# Board-Front.net
KiCad netlist of a schematic drawn in EAGLE
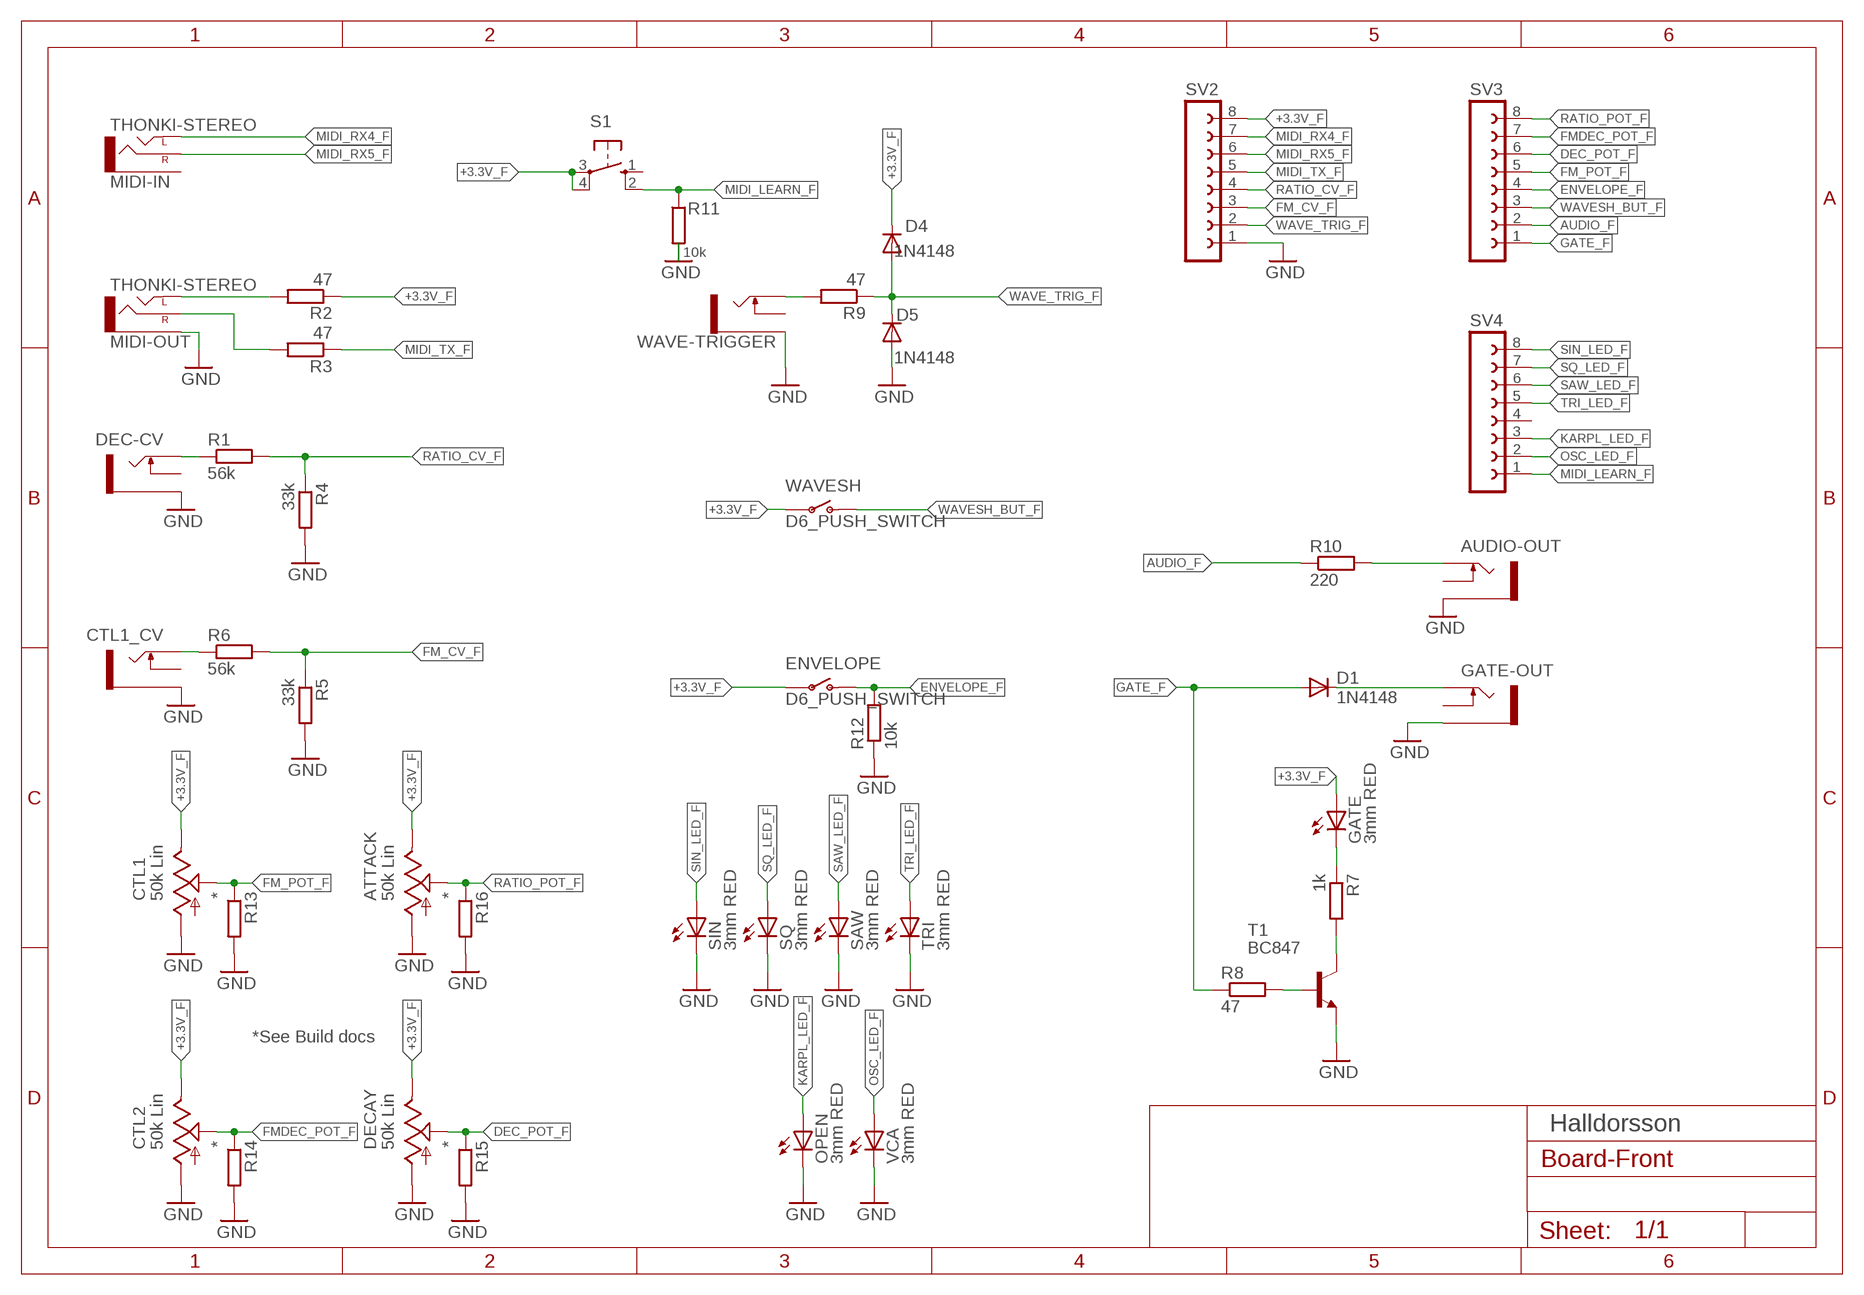
[diagram p0: schematic, sheet 1]

(export (version "E")
  (design (tool "Eeschema 10.0.6"))
  (components
    (comp (ref "ATTACK")
      (value "50k Lin")
      (footprint "eagle-import:9MM_SNAP-IN_POT")
      (libsource (lib "eagle-import") (part "9MM_SNAP-IN_POT_"))
    )
    (comp (ref "AUDIO-OUT")
      (value "THONKICONNNEW")
      (footprint "eagle-import:WQP-PJ301M-12_JACK")
      (libsource (lib "eagle-import") (part "THONKICONNNEW"))
    )
    (comp (ref "CTL1")
      (value "50k Lin")
      (footprint "eagle-import:9MM_SNAP-IN_POT")
      (libsource (lib "eagle-import") (part "9MM_SNAP-IN_POT_"))
    )
    (comp (ref "CTL1_CV")
      (value "THONKICONNNEW")
      (footprint "eagle-import:WQP-PJ301M-12_JACK")
      (libsource (lib "eagle-import") (part "THONKICONNNEW"))
    )
    (comp (ref "CTL2")
      (value "50k Lin")
      (footprint "eagle-import:9MM_SNAP-IN_POT")
      (libsource (lib "eagle-import") (part "9MM_SNAP-IN_POT_"))
    )
    (comp (ref "D1")
      (value "1N4148")
      (footprint "eagle-import:DO35-7")
      (libsource (lib "eagle-import") (part "1N4148DO35-7"))
    )
    (comp (ref "D4")
      (value "1N4148")
      (footprint "eagle-import:DO35-7")
      (libsource (lib "eagle-import") (part "1N4148DO35-7"))
    )
    (comp (ref "D5")
      (value "1N4148")
      (footprint "eagle-import:DO35-7")
      (libsource (lib "eagle-import") (part "1N4148DO35-7"))
    )
    (comp (ref "DEC-CV")
      (value "THONKICONNNEW")
      (footprint "eagle-import:WQP-PJ301M-12_JACK")
      (libsource (lib "eagle-import") (part "THONKICONNNEW"))
    )
    (comp (ref "DECAY")
      (value "50k Lin")
      (footprint "eagle-import:9MM_SNAP-IN_POT")
      (libsource (lib "eagle-import") (part "9MM_SNAP-IN_POT_"))
    )
    (comp (ref "ENVELOPE")
      (value "D6_PUSH_SWITCH")
      (footprint "eagle-import:D6_PUSH_SWITCH")
      (libsource (lib "eagle-import") (part "D6_PUSH_SWITCH"))
    )
    (comp (ref "GATE")
      (value "3mm RED")
      (footprint "eagle-import:LED3MM")
      (libsource (lib "eagle-import") (part "LED3MM"))
    )
    (comp (ref "GATE-OUT")
      (value "THONKICONNNEW")
      (footprint "eagle-import:WQP-PJ301M-12_JACK")
      (libsource (lib "eagle-import") (part "THONKICONNNEW"))
    )
    (comp (ref "MIDI-IN")
      (value "THONKI-STEREO")
      (footprint "eagle-import:WQP-PJ366ST_JACK")
      (libsource (lib "eagle-import") (part "THONKI-STEREO"))
    )
    (comp (ref "MIDI-OUT")
      (value "THONKI-STEREO")
      (footprint "eagle-import:WQP-PJ366ST_JACK")
      (libsource (lib "eagle-import") (part "THONKI-STEREO"))
    )
    (comp (ref "OPEN")
      (value "3mm RED")
      (footprint "eagle-import:LED3MM")
      (libsource (lib "eagle-import") (part "LED3MM"))
    )
    (comp (ref "R1")
      (value "56k")
      (footprint "eagle-import:M1206")
      (libsource (lib "eagle-import") (part "R-EU_M1206"))
    )
    (comp (ref "R2")
      (value "47")
      (footprint "eagle-import:M1206")
      (libsource (lib "eagle-import") (part "R-EU_M1206"))
    )
    (comp (ref "R3")
      (value "47")
      (footprint "eagle-import:M1206")
      (libsource (lib "eagle-import") (part "R-EU_M1206"))
    )
    (comp (ref "R4")
      (value "33k")
      (footprint "eagle-import:M1206")
      (libsource (lib "eagle-import") (part "R-EU_M1206"))
    )
    (comp (ref "R5")
      (value "33k")
      (footprint "eagle-import:M1206")
      (libsource (lib "eagle-import") (part "R-EU_M1206"))
    )
    (comp (ref "R6")
      (value "56k")
      (footprint "eagle-import:M1206")
      (libsource (lib "eagle-import") (part "R-EU_M1206"))
    )
    (comp (ref "R7")
      (value "1k")
      (footprint "eagle-import:M1206")
      (libsource (lib "eagle-import") (part "R-EU_M1206"))
    )
    (comp (ref "R8")
      (value "47")
      (footprint "eagle-import:M1206")
      (libsource (lib "eagle-import") (part "R-EU_M1206"))
    )
    (comp (ref "R9")
      (value "47")
      (footprint "eagle-import:M1206")
      (libsource (lib "eagle-import") (part "R-EU_M1206"))
    )
    (comp (ref "R10")
      (value "220")
      (footprint "eagle-import:M1206")
      (libsource (lib "eagle-import") (part "R-EU_M1206"))
    )
    (comp (ref "R11")
      (value "10k")
      (footprint "eagle-import:M1206")
      (libsource (lib "eagle-import") (part "R-EU_M1206"))
    )
    (comp (ref "R12")
      (value "10k")
      (footprint "eagle-import:M1206")
      (libsource (lib "eagle-import") (part "R-EU_M1206"))
    )
    (comp (ref "R13")
      (value "*")
      (footprint "eagle-import:M1206")
      (libsource (lib "eagle-import") (part "R-EU_M1206"))
    )
    (comp (ref "R14")
      (value "*")
      (footprint "eagle-import:M1206")
      (libsource (lib "eagle-import") (part "R-EU_M1206"))
    )
    (comp (ref "R15")
      (value "*")
      (footprint "eagle-import:M1206")
      (libsource (lib "eagle-import") (part "R-EU_M1206"))
    )
    (comp (ref "R16")
      (value "*")
      (footprint "eagle-import:M1206")
      (libsource (lib "eagle-import") (part "R-EU_M1206"))
    )
    (comp (ref "S1")
      (value "10-XX")
      (footprint "eagle-import:B3F-10XX")
      (fields (field (name "MPN") "B3F-1000"))
      (libsource (lib "eagle-import") (part "10-XX"))
    )
    (comp (ref "SAW")
      (value "3mm RED")
      (footprint "eagle-import:LED3MM")
      (libsource (lib "eagle-import") (part "LED3MM"))
    )
    (comp (ref "SIN")
      (value "3mm RED")
      (footprint "eagle-import:LED3MM")
      (libsource (lib "eagle-import") (part "LED3MM"))
    )
    (comp (ref "SQ")
      (value "3mm RED")
      (footprint "eagle-import:LED3MM")
      (libsource (lib "eagle-import") (part "LED3MM"))
    )
    (comp (ref "SV2")
      (value "FE08-1")
      (footprint "eagle-import:FE08")
      (libsource (lib "eagle-import") (part "FE08-1"))
    )
    (comp (ref "SV3")
      (value "FE08-1")
      (footprint "eagle-import:FE08")
      (libsource (lib "eagle-import") (part "FE08-1"))
    )
    (comp (ref "SV4")
      (value "FE08-1")
      (footprint "eagle-import:FE08")
      (libsource (lib "eagle-import") (part "FE08-1"))
    )
    (comp (ref "T1")
      (value "BC847")
      (footprint "eagle-import:SOT23")
      (libsource (lib "eagle-import") (part "BC847"))
    )
    (comp (ref "TRI")
      (value "3mm RED")
      (footprint "eagle-import:LED3MM")
      (libsource (lib "eagle-import") (part "LED3MM"))
    )
    (comp (ref "VCA")
      (value "3mm RED")
      (footprint "eagle-import:LED3MM")
      (libsource (lib "eagle-import") (part "LED3MM"))
    )
    (comp (ref "WAVE-TRIGGER")
      (value "THONKICONNNEW")
      (footprint "eagle-import:WQP-PJ301M-12_JACK")
      (libsource (lib "eagle-import") (part "THONKICONNNEW"))
    )
    (comp (ref "WAVESH")
      (value "D6_PUSH_SWITCH")
      (footprint "eagle-import:D6_PUSH_SWITCH")
      (libsource (lib "eagle-import") (part "D6_PUSH_SWITCH"))
    )
  )
  (nets
    (net (code "1") (name "+3.3V_F") (class "Default")
      (node (ref "ATTACK") (pin "3") (pinfunction "E_3") (pintype "passive"))
      (node (ref "CTL1") (pin "3") (pinfunction "E_3") (pintype "passive"))
      (node (ref "CTL2") (pin "3") (pinfunction "E_3") (pintype "passive"))
      (node (ref "D4") (pin "C") (pinfunction "C_C") (pintype "passive"))
      (node (ref "DECAY") (pin "3") (pinfunction "E_3") (pintype "passive"))
      (node (ref "ENVELOPE") (pin "P$3") (pinfunction "P_P$3") (pintype "passive"))
      (node (ref "ENVELOPE") (pin "P$4") (pinfunction "P_P$4") (pintype "passive"))
      (node (ref "GATE") (pin "A") (pinfunction "A_A") (pintype "passive"))
      (node (ref "R2") (pin "1") (pinfunction "1_1") (pintype "passive"))
      (node (ref "S1") (pin "3") (pinfunction "P_3") (pintype "passive"))
      (node (ref "S1") (pin "4") (pinfunction "P1_4") (pintype "passive"))
      (node (ref "SV2") (pin "8") (pinfunction "8_8") (pintype "passive"))
      (node (ref "WAVESH") (pin "P$3") (pinfunction "P_P$3") (pintype "passive"))
      (node (ref "WAVESH") (pin "P$4") (pinfunction "P_P$4") (pintype "passive"))
    )
    (net (code "2") (name "AUDIO_F") (class "Default")
      (node (ref "R10") (pin "1") (pinfunction "1_1") (pintype "passive"))
      (node (ref "SV3") (pin "2") (pinfunction "2_2") (pintype "passive"))
    )
    (net (code "3") (name "DEC_POT_F") (class "Default")
      (node (ref "DECAY") (pin "2") (pinfunction "S_2") (pintype "passive"))
      (node (ref "R15") (pin "1") (pinfunction "1_1") (pintype "passive"))
      (node (ref "SV3") (pin "6") (pinfunction "6_6") (pintype "passive"))
    )
    (net (code "4") (name "ENVELOPE_F") (class "Default")
      (node (ref "ENVELOPE") (pin "P$1") (pinfunction "O_P$1") (pintype "passive"))
      (node (ref "ENVELOPE") (pin "P$2") (pinfunction "O_P$2") (pintype "passive"))
      (node (ref "R12") (pin "2") (pinfunction "2_2") (pintype "passive"))
      (node (ref "SV3") (pin "4") (pinfunction "4_4") (pintype "passive"))
    )
    (net (code "5") (name "FMDEC_POT_F") (class "Default")
      (node (ref "CTL2") (pin "2") (pinfunction "S_2") (pintype "passive"))
      (node (ref "R14") (pin "1") (pinfunction "1_1") (pintype "passive"))
      (node (ref "SV3") (pin "7") (pinfunction "7_7") (pintype "passive"))
    )
    (net (code "6") (name "FM_CV_F") (class "Default")
      (node (ref "R5") (pin "1") (pinfunction "1_1") (pintype "passive"))
      (node (ref "R6") (pin "2") (pinfunction "2_2") (pintype "passive"))
      (node (ref "SV2") (pin "3") (pinfunction "3_3") (pintype "passive"))
    )
    (net (code "7") (name "FM_POT_F") (class "Default")
      (node (ref "CTL1") (pin "2") (pinfunction "S_2") (pintype "passive"))
      (node (ref "R13") (pin "1") (pinfunction "1_1") (pintype "passive"))
      (node (ref "SV3") (pin "5") (pinfunction "5_5") (pintype "passive"))
    )
    (net (code "8") (name "GATE_F") (class "Default")
      (node (ref "D1") (pin "A") (pinfunction "A_A") (pintype "passive"))
      (node (ref "R8") (pin "1") (pinfunction "1_1") (pintype "passive"))
      (node (ref "SV3") (pin "1") (pinfunction "1_1") (pintype "passive"))
    )
    (net (code "9") (name "GND") (class "Default")
      (node (ref "ATTACK") (pin "1") (pinfunction "A_1") (pintype "passive"))
      (node (ref "AUDIO-OUT") (pin "P$3_SLEEVE") (pinfunction "SLEEVE_P$3_SLEEVE") (pintype "passive"))
      (node (ref "CTL1") (pin "1") (pinfunction "A_1") (pintype "passive"))
      (node (ref "CTL1_CV") (pin "P$3_SLEEVE") (pinfunction "SLEEVE_P$3_SLEEVE") (pintype "passive"))
      (node (ref "CTL2") (pin "1") (pinfunction "A_1") (pintype "passive"))
      (node (ref "D5") (pin "A") (pinfunction "A_A") (pintype "passive"))
      (node (ref "DEC-CV") (pin "P$3_SLEEVE") (pinfunction "SLEEVE_P$3_SLEEVE") (pintype "passive"))
      (node (ref "DECAY") (pin "1") (pinfunction "A_1") (pintype "passive"))
      (node (ref "GATE-OUT") (pin "P$3_SLEEVE") (pinfunction "SLEEVE_P$3_SLEEVE") (pintype "passive"))
      (node (ref "MIDI-OUT") (pin "P$3_SLEEVE") (pinfunction "SLEEVE_P$3_SLEEVE") (pintype "bidirectional"))
      (node (ref "OPEN") (pin "K") (pinfunction "C_K") (pintype "passive"))
      (node (ref "R11") (pin "2") (pinfunction "2_2") (pintype "passive"))
      (node (ref "R12") (pin "1") (pinfunction "1_1") (pintype "passive"))
      (node (ref "R13") (pin "2") (pinfunction "2_2") (pintype "passive"))
      (node (ref "R14") (pin "2") (pinfunction "2_2") (pintype "passive"))
      (node (ref "R15") (pin "2") (pinfunction "2_2") (pintype "passive"))
      (node (ref "R16") (pin "2") (pinfunction "2_2") (pintype "passive"))
      (node (ref "R4") (pin "2") (pinfunction "2_2") (pintype "passive"))
      (node (ref "R5") (pin "2") (pinfunction "2_2") (pintype "passive"))
      (node (ref "SAW") (pin "K") (pinfunction "C_K") (pintype "passive"))
      (node (ref "SIN") (pin "K") (pinfunction "C_K") (pintype "passive"))
      (node (ref "SQ") (pin "K") (pinfunction "C_K") (pintype "passive"))
      (node (ref "SV2") (pin "1") (pinfunction "1_1") (pintype "passive"))
      (node (ref "T1") (pin "2") (pinfunction "E_2") (pintype "passive"))
      (node (ref "TRI") (pin "K") (pinfunction "C_K") (pintype "passive"))
      (node (ref "VCA") (pin "K") (pinfunction "C_K") (pintype "passive"))
      (node (ref "WAVE-TRIGGER") (pin "P$3_SLEEVE") (pinfunction "SLEEVE_P$3_SLEEVE") (pintype "passive"))
    )
    (net (code "10") (name "KARPL_LED_F") (class "Default")
      (node (ref "OPEN") (pin "A") (pinfunction "A_A") (pintype "passive"))
      (node (ref "SV4") (pin "3") (pinfunction "3_3") (pintype "passive"))
    )
    (net (code "11") (name "MIDI_LEARN_F") (class "Default")
      (node (ref "R11") (pin "1") (pinfunction "1_1") (pintype "passive"))
      (node (ref "S1") (pin "2") (pinfunction "S1_2") (pintype "passive"))
      (node (ref "SV4") (pin "1") (pinfunction "1_1") (pintype "passive"))
    )
    (net (code "12") (name "MIDI_RX4_F") (class "Default")
      (node (ref "MIDI-IN") (pin "P$1_TIP") (pinfunction "LEFT_P$1_TIP") (pintype "bidirectional"))
      (node (ref "SV2") (pin "7") (pinfunction "7_7") (pintype "passive"))
    )
    (net (code "13") (name "MIDI_RX5_F") (class "Default")
      (node (ref "MIDI-IN") (pin "P$2_SWITCH") (pinfunction "RIGHT_P$2_SWITCH") (pintype "bidirectional"))
      (node (ref "SV2") (pin "6") (pinfunction "6_6") (pintype "passive"))
    )
    (net (code "14") (name "MIDI_TX_F") (class "Default")
      (node (ref "R3") (pin "1") (pinfunction "1_1") (pintype "passive"))
      (node (ref "SV2") (pin "5") (pinfunction "5_5") (pintype "passive"))
    )
    (net (code "15") (name "Net-(AUDIO-OUT-TIP)") (class "Default")
      (node (ref "AUDIO-OUT") (pin "P$1_TIP") (pinfunction "TIP_P$1_TIP") (pintype "passive"))
      (node (ref "R10") (pin "2") (pinfunction "2_2") (pintype "passive"))
    )
    (net (code "16") (name "Net-(CTL1_CV-TIP)") (class "Default")
      (node (ref "CTL1_CV") (pin "P$1_TIP") (pinfunction "TIP_P$1_TIP") (pintype "passive"))
      (node (ref "R6") (pin "1") (pinfunction "1_1") (pintype "passive"))
    )
    (net (code "17") (name "Net-(DEC-CV-TIP)") (class "Default")
      (node (ref "DEC-CV") (pin "P$1_TIP") (pinfunction "TIP_P$1_TIP") (pintype "passive"))
      (node (ref "R1") (pin "1") (pinfunction "1_1") (pintype "passive"))
    )
    (net (code "18") (name "Net-(GATE-C)") (class "Default")
      (node (ref "GATE") (pin "K") (pinfunction "C_K") (pintype "passive"))
      (node (ref "R7") (pin "1") (pinfunction "1_1") (pintype "passive"))
    )
    (net (code "19") (name "Net-(GATE-OUT-TIP)") (class "Default")
      (node (ref "D1") (pin "C") (pinfunction "C_C") (pintype "passive"))
      (node (ref "GATE-OUT") (pin "P$1_TIP") (pinfunction "TIP_P$1_TIP") (pintype "passive"))
    )
    (net (code "20") (name "Net-(MIDI-OUT-LEFT)") (class "Default")
      (node (ref "MIDI-OUT") (pin "P$1_TIP") (pinfunction "LEFT_P$1_TIP") (pintype "bidirectional"))
      (node (ref "R2") (pin "2") (pinfunction "2_2") (pintype "passive"))
    )
    (net (code "21") (name "Net-(MIDI-OUT-RIGHT)") (class "Default")
      (node (ref "MIDI-OUT") (pin "P$2_SWITCH") (pinfunction "RIGHT_P$2_SWITCH") (pintype "bidirectional"))
      (node (ref "R3") (pin "2") (pinfunction "2_2") (pintype "passive"))
    )
    (net (code "22") (name "Net-(T1-B)") (class "Default")
      (node (ref "R8") (pin "2") (pinfunction "2_2") (pintype "passive"))
      (node (ref "T1") (pin "1") (pinfunction "B_1") (pintype "passive"))
    )
    (net (code "23") (name "Net-(T1-C)") (class "Default")
      (node (ref "R7") (pin "2") (pinfunction "2_2") (pintype "passive"))
      (node (ref "T1") (pin "3") (pinfunction "C_3") (pintype "passive"))
    )
    (net (code "24") (name "Net-(WAVE-TRIGGER-TIP)") (class "Default")
      (node (ref "R9") (pin "2") (pinfunction "2_2") (pintype "passive"))
      (node (ref "WAVE-TRIGGER") (pin "P$1_TIP") (pinfunction "TIP_P$1_TIP") (pintype "passive"))
    )
    (net (code "25") (name "OSC_LED_F") (class "Default")
      (node (ref "SV4") (pin "2") (pinfunction "2_2") (pintype "passive"))
      (node (ref "VCA") (pin "A") (pinfunction "A_A") (pintype "passive"))
    )
    (net (code "26") (name "RATIO_CV_F") (class "Default")
      (node (ref "R1") (pin "2") (pinfunction "2_2") (pintype "passive"))
      (node (ref "R4") (pin "1") (pinfunction "1_1") (pintype "passive"))
      (node (ref "SV2") (pin "4") (pinfunction "4_4") (pintype "passive"))
    )
    (net (code "27") (name "RATIO_POT_F") (class "Default")
      (node (ref "ATTACK") (pin "2") (pinfunction "S_2") (pintype "passive"))
      (node (ref "R16") (pin "1") (pinfunction "1_1") (pintype "passive"))
      (node (ref "SV3") (pin "8") (pinfunction "8_8") (pintype "passive"))
    )
    (net (code "28") (name "SAW_LED_F") (class "Default")
      (node (ref "SAW") (pin "A") (pinfunction "A_A") (pintype "passive"))
      (node (ref "SV4") (pin "6") (pinfunction "6_6") (pintype "passive"))
    )
    (net (code "29") (name "SIN_LED_F") (class "Default")
      (node (ref "SIN") (pin "A") (pinfunction "A_A") (pintype "passive"))
      (node (ref "SV4") (pin "8") (pinfunction "8_8") (pintype "passive"))
    )
    (net (code "30") (name "SQ_LED_F") (class "Default")
      (node (ref "SQ") (pin "A") (pinfunction "A_A") (pintype "passive"))
      (node (ref "SV4") (pin "7") (pinfunction "7_7") (pintype "passive"))
    )
    (net (code "31") (name "TRI_LED_F") (class "Default")
      (node (ref "SV4") (pin "5") (pinfunction "5_5") (pintype "passive"))
      (node (ref "TRI") (pin "A") (pinfunction "A_A") (pintype "passive"))
    )
    (net (code "32") (name "WAVESH_BUT_F") (class "Default")
      (node (ref "SV3") (pin "3") (pinfunction "3_3") (pintype "passive"))
      (node (ref "WAVESH") (pin "P$1") (pinfunction "O_P$1") (pintype "passive"))
      (node (ref "WAVESH") (pin "P$2") (pinfunction "O_P$2") (pintype "passive"))
    )
    (net (code "33") (name "WAVE_TRIG_F") (class "Default")
      (node (ref "D4") (pin "A") (pinfunction "A_A") (pintype "passive"))
      (node (ref "D5") (pin "C") (pinfunction "C_C") (pintype "passive"))
      (node (ref "R9") (pin "1") (pinfunction "1_1") (pintype "passive"))
      (node (ref "SV2") (pin "2") (pinfunction "2_2") (pintype "passive"))
    )
    (net (code "34") (name "unconnected-(AUDIO-OUT-SWITCH-PadP$2_SWITCH)") (class "Default")
      (node (ref "AUDIO-OUT") (pin "P$2_SWITCH") (pinfunction "SWITCH_P$2_SWITCH") (pintype "passive"))
    )
    (net (code "35") (name "unconnected-(CTL1_CV-SWITCH-PadP$2_SWITCH)") (class "Default")
      (node (ref "CTL1_CV") (pin "P$2_SWITCH") (pinfunction "SWITCH_P$2_SWITCH") (pintype "passive"))
    )
    (net (code "36") (name "unconnected-(DEC-CV-SWITCH-PadP$2_SWITCH)") (class "Default")
      (node (ref "DEC-CV") (pin "P$2_SWITCH") (pinfunction "SWITCH_P$2_SWITCH") (pintype "passive"))
    )
    (net (code "37") (name "unconnected-(GATE-OUT-SWITCH-PadP$2_SWITCH)") (class "Default")
      (node (ref "GATE-OUT") (pin "P$2_SWITCH") (pinfunction "SWITCH_P$2_SWITCH") (pintype "passive"))
    )
    (net (code "38") (name "unconnected-(MIDI-IN-SLEEVE-PadP$3_SLEEVE)") (class "Default")
      (node (ref "MIDI-IN") (pin "P$3_SLEEVE") (pinfunction "SLEEVE_P$3_SLEEVE") (pintype "bidirectional"))
    )
    (net (code "39") (name "unconnected-(S1-S-Pad1)") (class "Default")
      (node (ref "S1") (pin "1") (pinfunction "S_1") (pintype "passive"))
    )
    (net (code "40") (name "unconnected-(SV4-Pad4)") (class "Default")
      (node (ref "SV4") (pin "4") (pinfunction "4_4") (pintype "passive"))
    )
    (net (code "41") (name "unconnected-(WAVE-TRIGGER-SWITCH-PadP$2_SWITCH)") (class "Default")
      (node (ref "WAVE-TRIGGER") (pin "P$2_SWITCH") (pinfunction "SWITCH_P$2_SWITCH") (pintype "passive"))
    )
  )
)
